# final_clock.net
KiCad netlist of a schematic drawn in Altium Designer
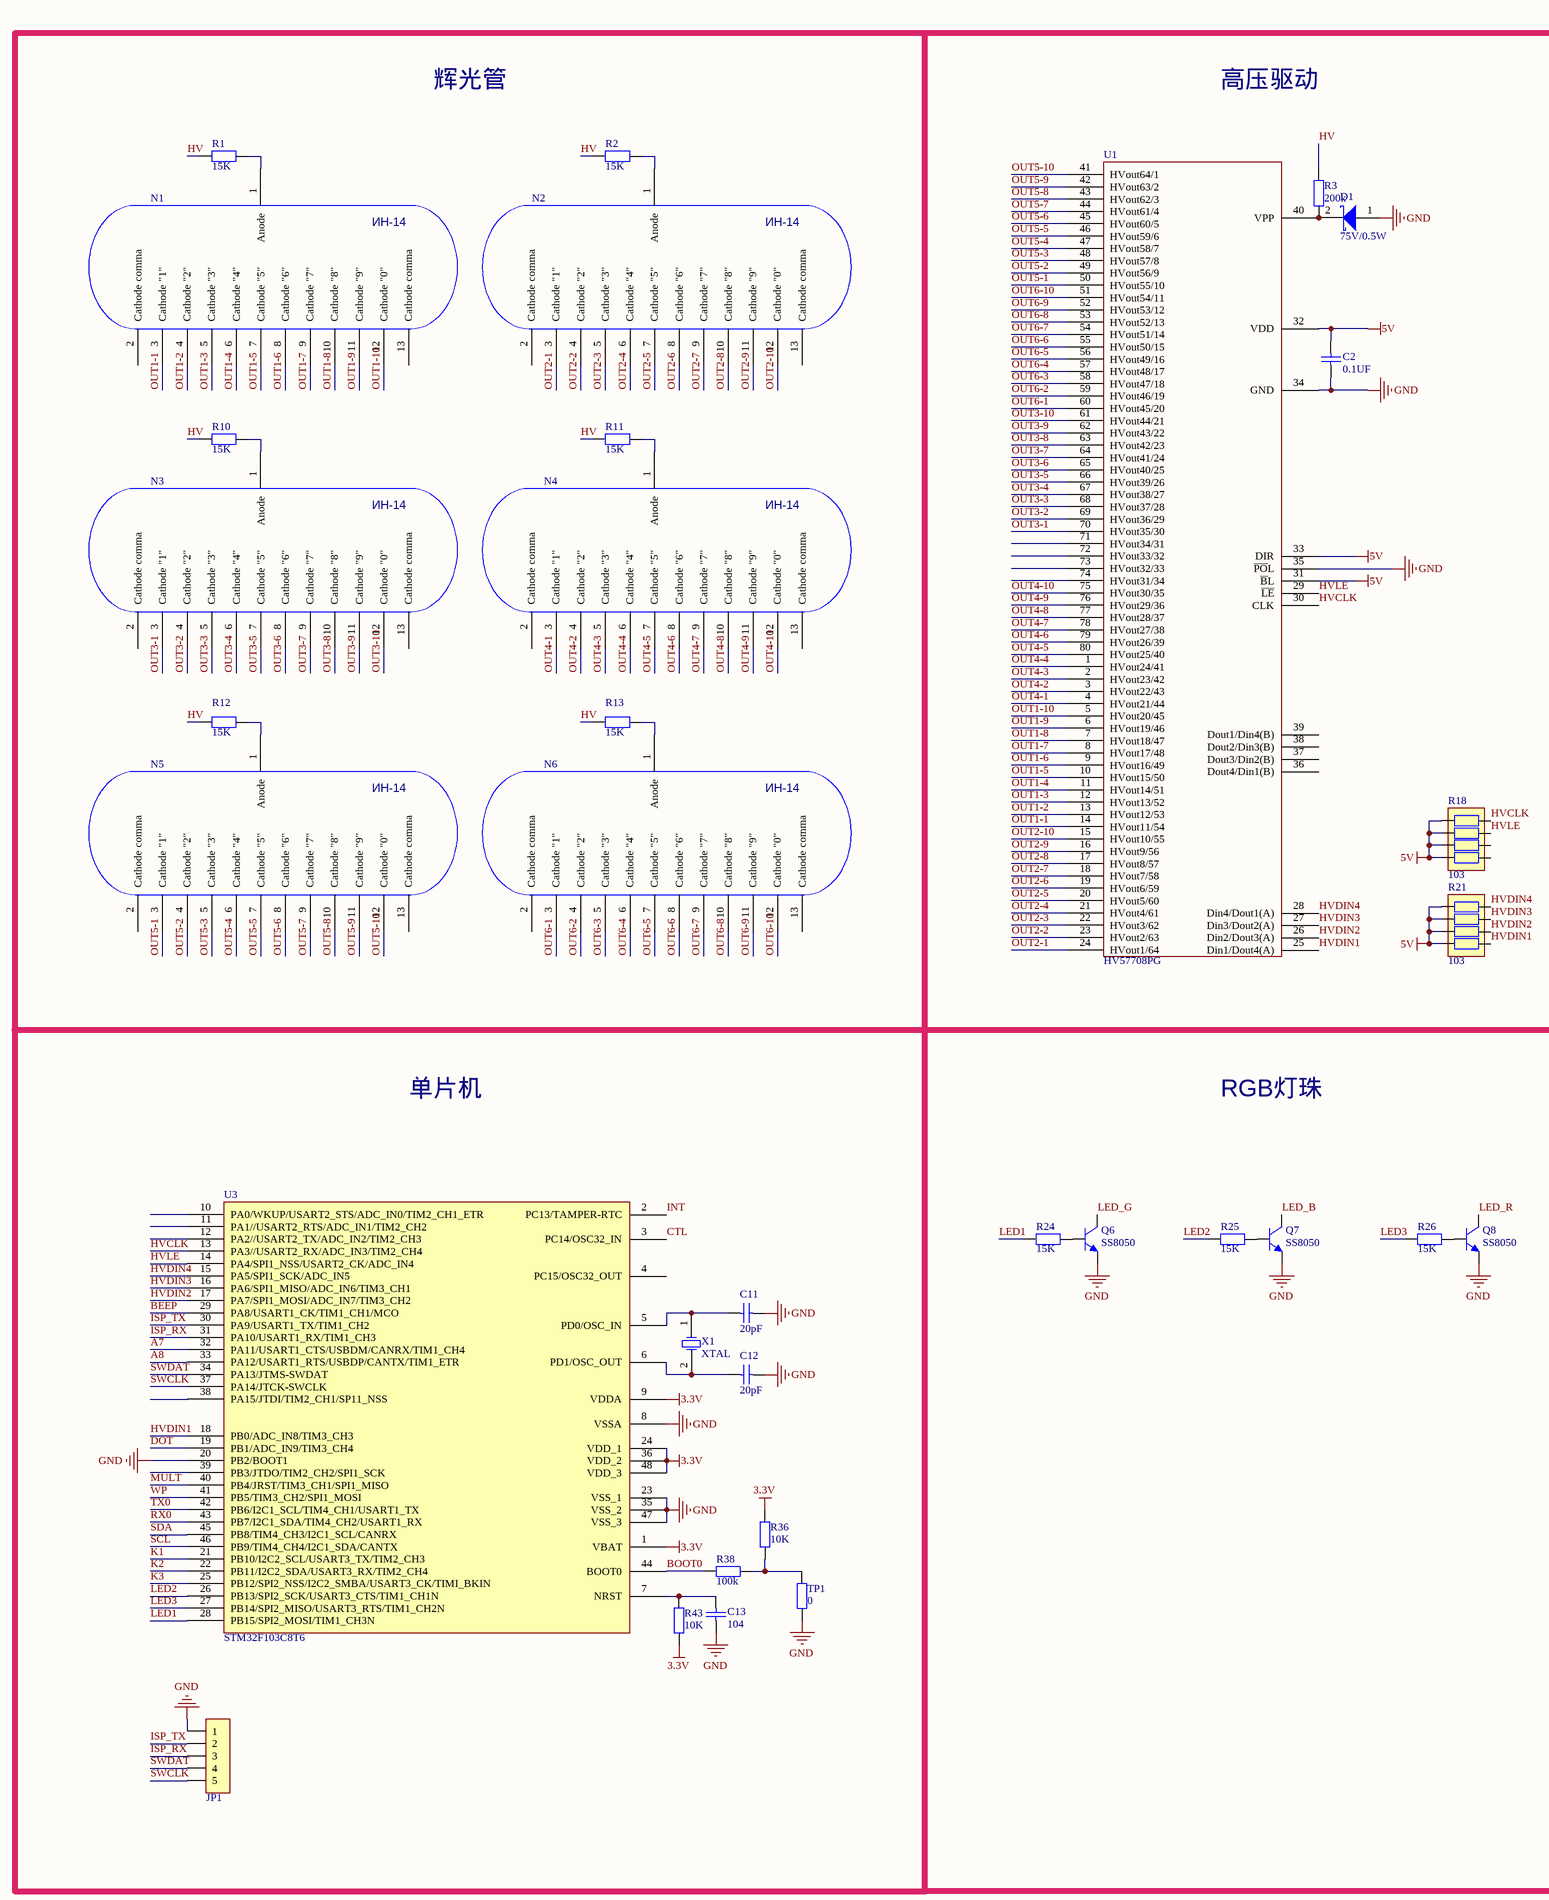
[diagram p0: final_clock.SchDoc, left]
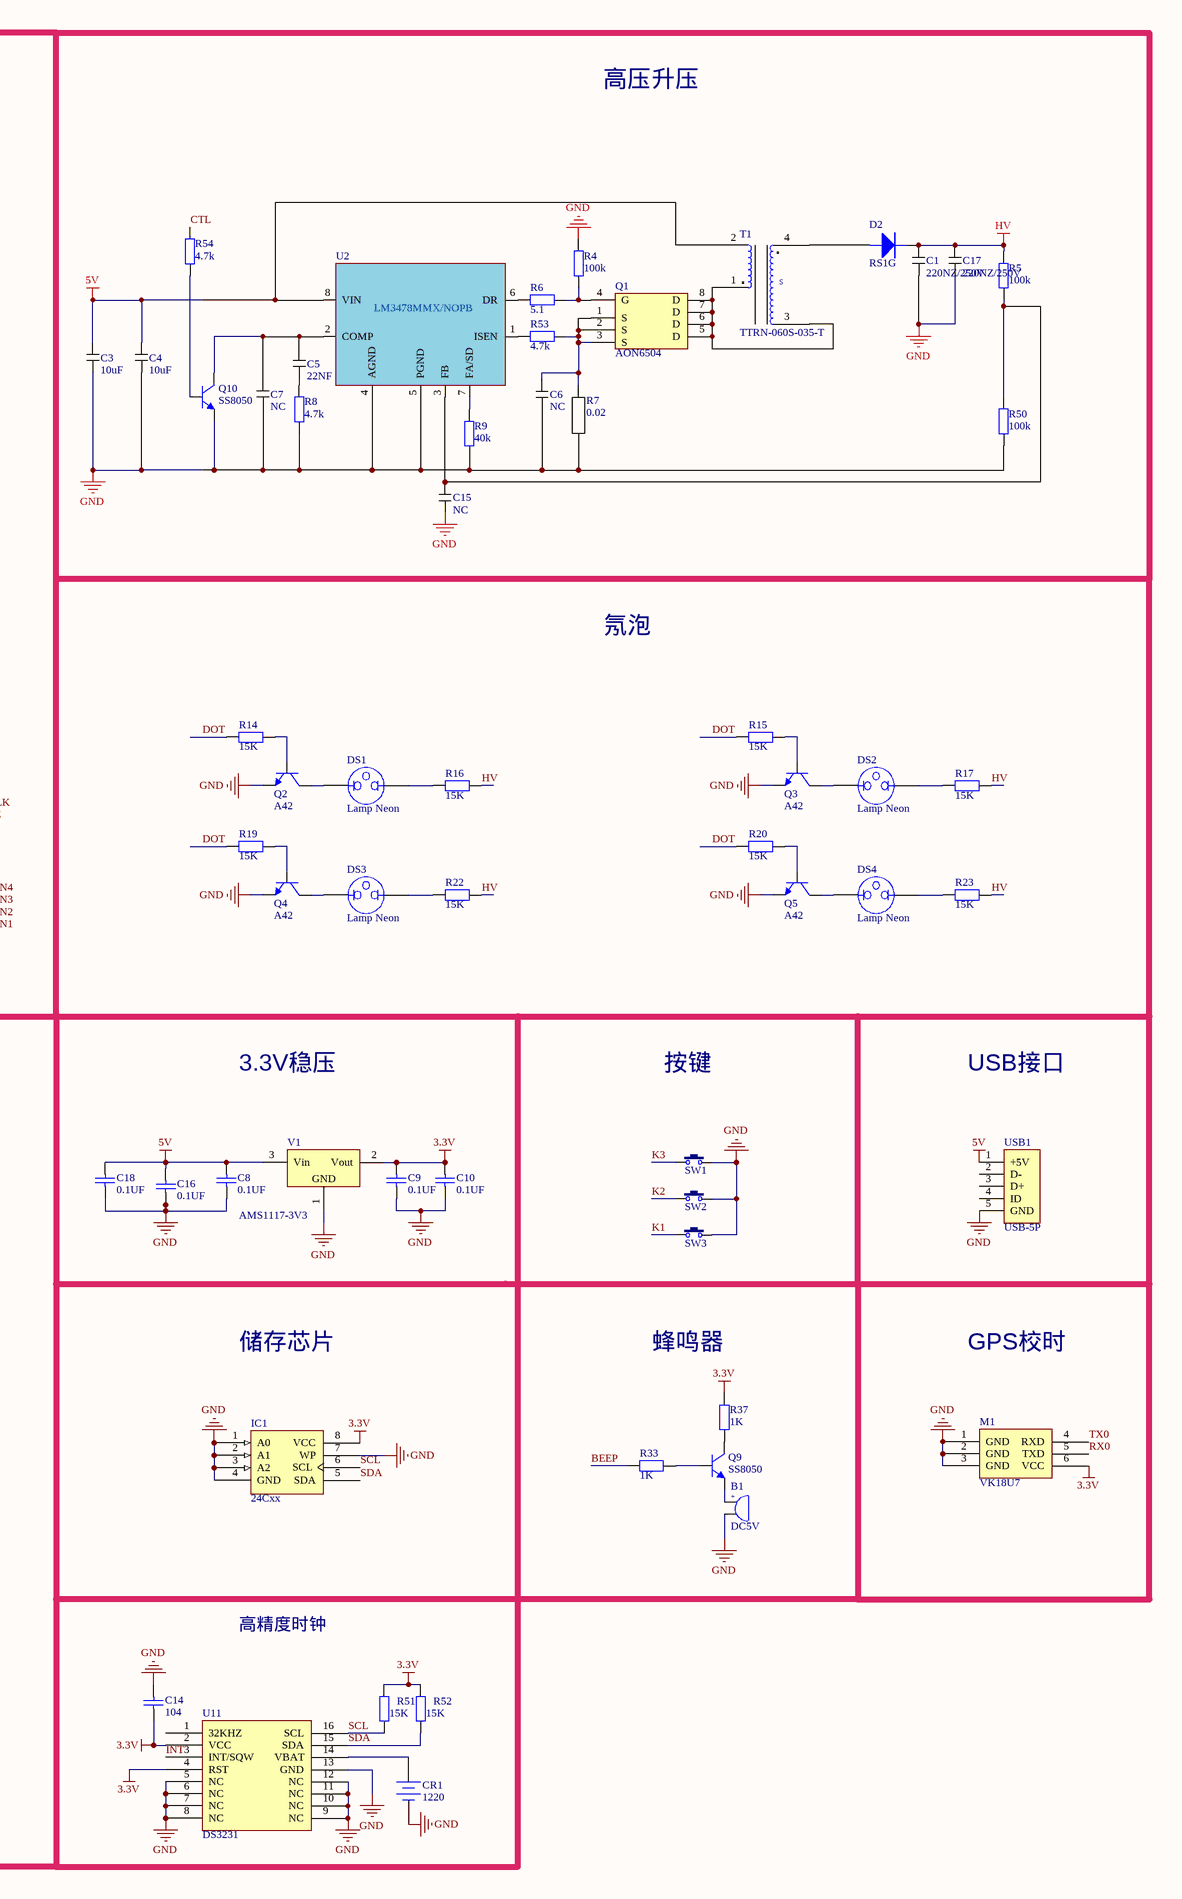
[diagram p1: final_clock.SchDoc, right]

(export (version "E")
  (design (tool "Eeschema 10.0.6"))
  (components
    (comp (ref "B1")
      (value "DC5V")
      (footprint "贴片蜂鸣器")
      (description "蜂鸣器")
      (fields (field (name "版权归属") "源创客"))
      (libsource (lib "未分类器件") (part "BEEP"))
    )
    (comp (ref "C1")
      (value "220NZ/250V")
      (footprint "C 1812")
      (description "无极性电容")
      (libsource (lib "贴片电容") (part "CAP"))
    )
    (comp (ref "C2")
      (value "0.1UF")
      (footprint "C 0805")
      (description "Capacitor")
      (fields (field (name "Comment") "Cap") (field (name "PUBLISHER") "Altium Limited"))
      (libsource (lib "Miscellaneous Devices") (part "Cap"))
    )
    (comp (ref "C3")
      (value "10uF")
      (footprint "C 1812")
      (description "无极性电容")
      (libsource (lib "贴片电容") (part "CAP"))
    )
    (comp (ref "C4")
      (value "10uF")
      (footprint "C 1812")
      (description "无极性电容")
      (libsource (lib "贴片电容") (part "CAP"))
    )
    (comp (ref "C5")
      (value "22NF")
      (footprint "C 0805")
      (description "无极性电容")
      (libsource (lib "贴片电容") (part "CAP"))
    )
    (comp (ref "C6")
      (value "NC")
      (footprint "C 0805")
      (description "无极性电容")
      (libsource (lib "贴片电容") (part "CAP"))
    )
    (comp (ref "C7")
      (value "NC")
      (footprint "C 0805")
      (description "无极性电容")
      (libsource (lib "贴片电容") (part "CAP"))
    )
    (comp (ref "C8")
      (value "0.1UF")
      (footprint "C 0805")
      (description "Capacitor")
      (fields (field (name "Comment") "Cap") (field (name "PUBLISHER") "Altium Limited"))
      (libsource (lib "Miscellaneous Devices") (part "Cap"))
    )
    (comp (ref "C9")
      (value "0.1UF")
      (footprint "C 0805")
      (description "Capacitor")
      (fields (field (name "Comment") "Cap") (field (name "PUBLISHER") "Altium Limited"))
      (libsource (lib "Miscellaneous Devices") (part "Cap"))
    )
    (comp (ref "C10")
      (value "0.1UF")
      (footprint "C 0805")
      (description "Capacitor")
      (fields (field (name "Comment") "Cap") (field (name "PUBLISHER") "Altium Limited"))
      (libsource (lib "Miscellaneous Devices") (part "Cap"))
    )
    (comp (ref "C11")
      (value "20pF")
      (footprint "C 0805")
      (description "Capacitor")
      (fields (field (name "Comment") "Cap") (field (name "PUBLISHER") "Altium Limited"))
      (libsource (lib "Miscellaneous Devices") (part "Cap"))
    )
    (comp (ref "C12")
      (value "20pF")
      (footprint "C 0805")
      (description "Capacitor")
      (fields (field (name "Comment") "Cap") (field (name "PUBLISHER") "Altium Limited"))
      (libsource (lib "Miscellaneous Devices") (part "Cap"))
    )
    (comp (ref "C13")
      (value "104")
      (footprint "C 0805")
      (description "Capacitor")
      (fields (field (name "Comment") "Cap") (field (name "PUBLISHER") "Altium Limited"))
      (libsource (lib "Miscellaneous Devices") (part "Cap"))
    )
    (comp (ref "C14")
      (value "104")
      (footprint "C 0805")
      (description "Capacitor")
      (fields (field (name "Comment") "Cap") (field (name "PUBLISHER") "Altium Limited"))
      (libsource (lib "Miscellaneous Devices") (part "Cap"))
    )
    (comp (ref "C15")
      (value "NC")
      (footprint "C 0805")
      (description "无极性电容")
      (libsource (lib "贴片电容") (part "CAP"))
    )
    (comp (ref "C16")
      (value "0.1UF")
      (footprint "C 0805")
      (description "Capacitor")
      (fields (field (name "Comment") "Cap") (field (name "PUBLISHER") "Altium Limited"))
      (libsource (lib "Miscellaneous Devices") (part "Cap"))
    )
    (comp (ref "C17")
      (value "220NZ/250V")
      (footprint "C 1812")
      (description "无极性电容")
      (libsource (lib "贴片电容") (part "CAP"))
    )
    (comp (ref "C18")
      (value "0.1UF")
      (footprint "C 0805")
      (description "Capacitor")
      (fields (field (name "Comment") "Cap") (field (name "PUBLISHER") "Altium Limited"))
      (libsource (lib "Miscellaneous Devices") (part "Cap"))
    )
    (comp (ref "CR1")
      (value "1220")
      (footprint "CR1220_A")
      (description "微型电池")
      (fields (field (name "版权归属") "源创客"))
      (libsource (lib "未分类器件") (part "CR-3V"))
    )
    (comp (ref "D1")
      (value "75V/0.5W")
      (footprint "R 1206")
      (description "Schottky Rectifier")
      (fields (field (name "PUBLISHER") "Altium Limited"))
      (libsource (lib "Miscellaneous Devices") (part "Diode 10TQ040"))
    )
    (comp (ref "D2")
      (value "RS1G")
      (footprint "SMA")
      (description "贴片快恢复二极管")
      (libsource (lib "二极管") (part "RS1G"))
    )
    (comp (ref "DS1")
      (value "Lamp Neon")
      (footprint "LED_PIN2")
      (description "Neon Lamp")
      (fields (field (name "PUBLISHER") "Altium Limited"))
      (libsource (lib "Miscellaneous Devices") (part "Lamp Neon"))
    )
    (comp (ref "DS2")
      (value "Lamp Neon")
      (footprint "LED_PIN2")
      (description "Neon Lamp")
      (fields (field (name "PUBLISHER") "Altium Limited"))
      (libsource (lib "Miscellaneous Devices") (part "Lamp Neon"))
    )
    (comp (ref "DS3")
      (value "Lamp Neon")
      (footprint "LED_PIN2")
      (description "Neon Lamp")
      (fields (field (name "PUBLISHER") "Altium Limited"))
      (libsource (lib "Miscellaneous Devices") (part "Lamp Neon"))
    )
    (comp (ref "DS4")
      (value "Lamp Neon")
      (footprint "LED_PIN2")
      (description "Neon Lamp")
      (fields (field (name "PUBLISHER") "Altium Limited"))
      (libsource (lib "Miscellaneous Devices") (part "Lamp Neon"))
    )
    (comp (ref "IC1")
      (value "24Cxx")
      (footprint "SOP8_L")
      (description "外置EEPROM")
      (fields (field (name "版权归属") "源创客"))
      (libsource (lib "IC芯片") (part "24Cxx"))
    )
    (comp (ref "JP1")
      (value "HDR-1X5")
      (footprint "HDR-1X5")
      (description "5P接插件")
      (fields (field (name "版权归属") "源创客"))
      (libsource (lib "接插件") (part "Header 5"))
    )
    (comp (ref "M1") (value "VK18U7") (footprint "VK18U7") (libsource (lib "module_lib") (part "VK18U7")))
    (comp (ref "N1") (value "ИН-14") (footprint "IN14") (libsource (lib "NIXIEClock_SCHLib") (part "ИН-14")))
    (comp (ref "N2") (value "ИН-14") (footprint "IN14") (libsource (lib "NIXIEClock_SCHLib") (part "ИН-14")))
    (comp (ref "N3") (value "ИН-14") (footprint "IN14") (libsource (lib "NIXIEClock_SCHLib") (part "ИН-14")))
    (comp (ref "N4") (value "ИН-14") (footprint "IN14") (libsource (lib "NIXIEClock_SCHLib") (part "ИН-14")))
    (comp (ref "N5") (value "ИН-14") (footprint "IN14") (libsource (lib "NIXIEClock_SCHLib") (part "ИН-14")))
    (comp (ref "N6") (value "ИН-14") (footprint "IN14") (libsource (lib "NIXIEClock_SCHLib") (part "ИН-14")))
    (comp (ref "Q1")
      (value "AON6504")
      (footprint "DFN-MOS")
      (description "N沟道MOS管")
      (libsource (lib "MOS管") (part "AON6504"))
    )
    (comp (ref "Q2")
      (value "A42")
      (footprint "SOT23-3L")
      (description "高频放大-NPN型")
      (fields (field (name "版权归属") "源创客"))
      (libsource (lib "三极管") (part "8050-SMD"))
    )
    (comp (ref "Q3")
      (value "A42")
      (footprint "SOT23-3L")
      (description "高频放大-NPN型")
      (fields (field (name "版权归属") "源创客"))
      (libsource (lib "三极管") (part "8050-SMD"))
    )
    (comp (ref "Q4")
      (value "A42")
      (footprint "SOT23-3L")
      (description "高频放大-NPN型")
      (fields (field (name "版权归属") "源创客"))
      (libsource (lib "三极管") (part "8050-SMD"))
    )
    (comp (ref "Q5")
      (value "A42")
      (footprint "SOT23-3L")
      (description "高频放大-NPN型")
      (fields (field (name "版权归属") "源创客"))
      (libsource (lib "三极管") (part "8050-SMD"))
    )
    (comp (ref "Q6")
      (value "SS8050")
      (footprint "SOT23-3L")
      (description "高频放大-NPN型")
      (fields (field (name "版权归属") "源创客"))
      (libsource (lib "三极管") (part "8050-SMD"))
    )
    (comp (ref "Q7")
      (value "SS8050")
      (footprint "SOT23-3L")
      (description "高频放大-NPN型")
      (fields (field (name "版权归属") "源创客"))
      (libsource (lib "三极管") (part "8050-SMD"))
    )
    (comp (ref "Q8")
      (value "SS8050")
      (footprint "SOT23-3L")
      (description "高频放大-NPN型")
      (fields (field (name "版权归属") "源创客"))
      (libsource (lib "三极管") (part "8050-SMD"))
    )
    (comp (ref "Q9")
      (value "SS8050")
      (footprint "SOT23-3L")
      (description "高频放大-NPN型")
      (fields (field (name "版权归属") "源创客"))
      (libsource (lib "三极管") (part "8050-SMD"))
    )
    (comp (ref "Q10")
      (value "SS8050")
      (footprint "SOT23-3L")
      (description "高频放大-NPN型")
      (fields (field (name "版权归属") "源创客"))
      (libsource (lib "三极管") (part "8050-SMD"))
    )
    (comp (ref "R1")
      (value "15K")
      (footprint "R 0805")
      (description "Resistor")
      (fields (field (name "Comment") "Res2") (field (name "PUBLISHER") "Altium Limited"))
      (libsource (lib "") (part "Res2_2"))
    )
    (comp (ref "R2")
      (value "15K")
      (footprint "R 0805")
      (description "Resistor")
      (fields (field (name "Comment") "Res2") (field (name "PUBLISHER") "Altium Limited"))
      (libsource (lib "") (part "Res2_2"))
    )
    (comp (ref "R3")
      (value "200k")
      (footprint "R 0805")
      (description "Resistor")
      (fields (field (name "Comment") "Res2") (field (name "PUBLISHER") "Altium Limited"))
      (libsource (lib "") (part "Res2_1"))
    )
    (comp (ref "R4")
      (value "100k")
      (footprint "R 0805")
      (description "Resistor")
      (fields (field (name "Comment") "Res2") (field (name "PUBLISHER") "Altium Limited"))
      (libsource (lib "") (part "Res2_1"))
    )
    (comp (ref "R5")
      (value "100k")
      (footprint "R 0805")
      (description "Resistor")
      (fields (field (name "Comment") "Res2") (field (name "PUBLISHER") "Altium Limited"))
      (libsource (lib "") (part "Res2_1"))
    )
    (comp (ref "R6")
      (value "5.1")
      (footprint "R 0805")
      (description "Resistor")
      (fields (field (name "Comment") "Res2") (field (name "PUBLISHER") "Altium Limited"))
      (libsource (lib "Miscellaneous Devices") (part "Res2"))
    )
    (comp (ref "R7") (value "0.02") (footprint "R 1206") (libsource (lib "贴片电阻") (part "RES")))
    (comp (ref "R8")
      (value "4.7k")
      (footprint "R 0805")
      (description "Resistor")
      (fields (field (name "Comment") "Res2") (field (name "PUBLISHER") "Altium Limited"))
      (libsource (lib "") (part "Res2_1"))
    )
    (comp (ref "R9")
      (value "40k")
      (footprint "R 0805")
      (description "Resistor")
      (fields (field (name "Comment") "Res2") (field (name "PUBLISHER") "Altium Limited"))
      (libsource (lib "") (part "Res2_1"))
    )
    (comp (ref "R10")
      (value "15K")
      (footprint "R 0805")
      (description "Resistor")
      (fields (field (name "Comment") "Res2") (field (name "PUBLISHER") "Altium Limited"))
      (libsource (lib "") (part "Res2_2"))
    )
    (comp (ref "R11")
      (value "15K")
      (footprint "R 0805")
      (description "Resistor")
      (fields (field (name "Comment") "Res2") (field (name "PUBLISHER") "Altium Limited"))
      (libsource (lib "") (part "Res2_2"))
    )
    (comp (ref "R12")
      (value "15K")
      (footprint "R 0805")
      (description "Resistor")
      (fields (field (name "Comment") "Res2") (field (name "PUBLISHER") "Altium Limited"))
      (libsource (lib "") (part "Res2_2"))
    )
    (comp (ref "R13")
      (value "15K")
      (footprint "R 0805")
      (description "Resistor")
      (fields (field (name "Comment") "Res2") (field (name "PUBLISHER") "Altium Limited"))
      (libsource (lib "") (part "Res2_2"))
    )
    (comp (ref "R14")
      (value "15K")
      (footprint "R 0805")
      (description "Resistor")
      (fields (field (name "Comment") "Res2") (field (name "PUBLISHER") "Altium Limited"))
      (libsource (lib "") (part "Res2_2"))
    )
    (comp (ref "R15")
      (value "15K")
      (footprint "R 0805")
      (description "Resistor")
      (fields (field (name "Comment") "Res2") (field (name "PUBLISHER") "Altium Limited"))
      (libsource (lib "") (part "Res2_2"))
    )
    (comp (ref "R16")
      (value "15K")
      (footprint "R 0805")
      (description "Resistor")
      (fields (field (name "Comment") "Res2") (field (name "PUBLISHER") "Altium Limited"))
      (libsource (lib "") (part "Res2_2"))
    )
    (comp (ref "R17")
      (value "15K")
      (footprint "R 0805")
      (description "Resistor")
      (fields (field (name "Comment") "Res2") (field (name "PUBLISHER") "Altium Limited"))
      (libsource (lib "") (part "Res2_2"))
    )
    (comp (ref "R18")
      (value "103")
      (footprint "RCA-8P4R-0603")
      (description "贴片网络排阻")
      (fields (field (name "版权归属") "源创客"))
      (libsource (lib "电阻-电容-电感") (part "R-8P4R"))
    )
    (comp (ref "R19")
      (value "15K")
      (footprint "R 0805")
      (description "Resistor")
      (fields (field (name "Comment") "Res2") (field (name "PUBLISHER") "Altium Limited"))
      (libsource (lib "") (part "Res2_2"))
    )
    (comp (ref "R20")
      (value "15K")
      (footprint "R 0805")
      (description "Resistor")
      (fields (field (name "Comment") "Res2") (field (name "PUBLISHER") "Altium Limited"))
      (libsource (lib "") (part "Res2_2"))
    )
    (comp (ref "R21")
      (value "103")
      (footprint "RCA-8P4R-0603")
      (description "贴片网络排阻")
      (fields (field (name "版权归属") "源创客"))
      (libsource (lib "电阻-电容-电感") (part "R-8P4R"))
    )
    (comp (ref "R22")
      (value "15K")
      (footprint "R 0805")
      (description "Resistor")
      (fields (field (name "Comment") "Res2") (field (name "PUBLISHER") "Altium Limited"))
      (libsource (lib "") (part "Res2_2"))
    )
    (comp (ref "R23")
      (value "15K")
      (footprint "R 0805")
      (description "Resistor")
      (fields (field (name "Comment") "Res2") (field (name "PUBLISHER") "Altium Limited"))
      (libsource (lib "") (part "Res2_2"))
    )
    (comp (ref "R24")
      (value "15K")
      (footprint "R 0805")
      (description "Resistor")
      (fields (field (name "Comment") "Res2") (field (name "PUBLISHER") "Altium Limited"))
      (libsource (lib "") (part "Res2_2"))
    )
    (comp (ref "R25")
      (value "15K")
      (footprint "R 0805")
      (description "Resistor")
      (fields (field (name "Comment") "Res2") (field (name "PUBLISHER") "Altium Limited"))
      (libsource (lib "") (part "Res2_2"))
    )
    (comp (ref "R26")
      (value "15K")
      (footprint "R 0805")
      (description "Resistor")
      (fields (field (name "Comment") "Res2") (field (name "PUBLISHER") "Altium Limited"))
      (libsource (lib "") (part "Res2_2"))
    )
    (comp (ref "R33")
      (value "1K")
      (footprint "R 0805")
      (description "Resistor")
      (fields (field (name "Comment") "Res2") (field (name "PUBLISHER") "Altium Limited"))
      (libsource (lib "Miscellaneous Devices") (part "Res2"))
    )
    (comp (ref "R36")
      (value "10K")
      (footprint "R 0805")
      (description "Resistor")
      (fields (field (name "Comment") "Res2") (field (name "PUBLISHER") "Altium Limited"))
      (libsource (lib "") (part "Res2_3"))
    )
    (comp (ref "R37")
      (value "1K")
      (footprint "R 0805")
      (description "Resistor")
      (fields (field (name "Comment") "Res2") (field (name "PUBLISHER") "Altium Limited"))
      (libsource (lib "") (part "Res2_3"))
    )
    (comp (ref "R38")
      (value "100k")
      (footprint "R 0805")
      (description "Resistor")
      (fields (field (name "Comment") "Res2") (field (name "PUBLISHER") "Altium Limited"))
      (libsource (lib "Miscellaneous Devices") (part "Res2"))
    )
    (comp (ref "R43")
      (value "10K")
      (footprint "R 0805")
      (description "Resistor")
      (fields (field (name "Comment") "Res2") (field (name "PUBLISHER") "Altium Limited"))
      (libsource (lib "") (part "Res2_1"))
    )
    (comp (ref "R50")
      (value "100k")
      (footprint "R 0805")
      (description "Resistor")
      (fields (field (name "Comment") "Res2") (field (name "PUBLISHER") "Altium Limited"))
      (libsource (lib "") (part "Res2_1"))
    )
    (comp (ref "R51")
      (value "15K")
      (footprint "R 0805")
      (description "Resistor")
      (fields (field (name "Comment") "Res2") (field (name "PUBLISHER") "Altium Limited"))
      (libsource (lib "") (part "Res2_1"))
    )
    (comp (ref "R52")
      (value "15K")
      (footprint "R 0805")
      (description "Resistor")
      (fields (field (name "Comment") "Res2") (field (name "PUBLISHER") "Altium Limited"))
      (libsource (lib "") (part "Res2_1"))
    )
    (comp (ref "R53")
      (value "4.7k")
      (footprint "R 0805")
      (description "Resistor")
      (fields (field (name "Comment") "Res2") (field (name "PUBLISHER") "Altium Limited"))
      (libsource (lib "Miscellaneous Devices") (part "Res2"))
    )
    (comp (ref "R54")
      (value "4.7k")
      (footprint "R 0805")
      (description "Resistor")
      (fields (field (name "Comment") "Res2") (field (name "PUBLISHER") "Altium Limited"))
      (libsource (lib "") (part "Res2_3"))
    )
    (comp (ref "SW1")
      (value "3x6x5")
      (footprint "贴片侧式按键")
      (description "3x6轻触开关")
      (fields (field (name "版权归属") "源创客"))
      (libsource (lib "按键-开关") (part "TSW 3x6"))
    )
    (comp (ref "SW2")
      (value "3x6x5")
      (footprint "贴片侧式按键")
      (description "3x6轻触开关")
      (fields (field (name "版权归属") "源创客"))
      (libsource (lib "按键-开关") (part "TSW 3x6"))
    )
    (comp (ref "SW3")
      (value "3x6x5")
      (footprint "贴片侧式按键")
      (description "3x6轻触开关")
      (fields (field (name "版权归属") "源创客"))
      (libsource (lib "按键-开关") (part "TSW 3x6"))
    )
    (comp (ref "T1")
      (value "TTRN-060S-035-T")
      (footprint "EE5.0")
      (description "闪光灯变压器")
      (libsource (lib "变压器") (part "TTRN-060S-035-T"))
    )
    (comp (ref "TP1")
      (value "0")
      (footprint "R 0805")
      (description "Resistor")
      (fields (field (name "Comment") "Res2") (field (name "PUBLISHER") "Altium Limited"))
      (libsource (lib "") (part "Res2_3"))
    )
    (comp (ref "U1") (value "HV57708PG") (footprint "CQFP80") (libsource (lib "SCH") (part "HV57708PG")))
    (comp (ref "U2")
      (value "LM3478MM")
      (footprint "SSOP8_N")
      (description "开关电源芯片")
      (fields
        (field (name "MANUFACTURER PART NUMBER") "LM3478MM/NOPB")
        (field (name "PACKAGEREFERENCE") "LM3478MMX/NOPB")
      )
      (libsource (lib "电源模块") (part "LM3478MM"))
    )
    (comp (ref "U3")
      (value "STM32F103C8T6")
      (footprint "LQFP48 7X7_N")
      (libsource (lib "Personal_Accumulation_Sch") (part "STM32F103C8T6"))
    )
    (comp (ref "U11") (value "DS3231") (footprint "SOP16W_M") (libsource (lib "ic_lib") (part "DS3231")))
    (comp (ref "USB1")
      (value "USB-5P")
      (footprint "USB-MICRO_A")
      (description "微型USB母座")
      (fields (field (name "版权归属") "源创客"))
      (libsource (lib "接口类") (part "USB-5P"))
    )
    (comp (ref "V1")
      (value "AMS1117-3V3")
      (footprint "_SOT-223")
      (description "三端稳压芯片")
      (fields (field (name "版权归属") "源创客"))
      (libsource (lib "IC芯片") (part "AMS1117"))
    )
    (comp (ref "X1")
      (value "XTAL")
      (footprint "5032-xtal")
      (description "Crystal Oscillator")
      (fields (field (name "PUBLISHER") "Altium Limited"))
      (libsource (lib "Miscellaneous Devices") (part "XTAL"))
    )
  )
  (nets
    (net (code "1") (name "/A7") (class "Default")
      (node (ref "U3") (pin "32") (pinfunction "PA11/USART1_CTS/USBDM/CANRX/TIM1_CH4_32") (pintype "passive"))
    )
    (net (code "2") (name "/A8") (class "Default")
      (node (ref "U3") (pin "33") (pinfunction "PA12/USART1_RTS/USBDP/CANTX/TIM1_ETR_33") (pintype "passive"))
    )
    (net (code "3") (name "/BEEP") (class "Default")
      (node (ref "R33") (pin "1") (pinfunction "1_1") (pintype "passive"))
      (node (ref "U3") (pin "29") (pinfunction "PA8/USART1_CK/TIM1_CH1/MCO_29") (pintype "passive"))
    )
    (net (code "4") (name "/BOOT0") (class "Default")
      (node (ref "R38") (pin "1") (pinfunction "1_1") (pintype "passive"))
      (node (ref "U3") (pin "44") (pinfunction "BOOT0_44") (pintype "passive"))
    )
    (net (code "5") (name "/CTL") (class "Default")
      (node (ref "R54") (pin "2") (pinfunction "2_2") (pintype "passive"))
      (node (ref "U3") (pin "3") (pinfunction "PC14/OSC32_IN_3") (pintype "passive"))
    )
    (net (code "6") (name "/DOT") (class "Default")
      (node (ref "R14") (pin "2") (pinfunction "2_2") (pintype "passive"))
      (node (ref "R15") (pin "2") (pinfunction "2_2") (pintype "passive"))
      (node (ref "R19") (pin "2") (pinfunction "2_2") (pintype "passive"))
      (node (ref "R20") (pin "2") (pinfunction "2_2") (pintype "passive"))
      (node (ref "U3") (pin "19") (pinfunction "PB1/ADC_IN9/TIM3_CH4_19") (pintype "passive"))
    )
    (net (code "7") (name "/HVCLK") (class "Default")
      (node (ref "R18") (pin "8") (pinfunction "8_8") (pintype "passive"))
      (node (ref "U1") (pin "30") (pinfunction "CLK_30") (pintype "passive"))
      (node (ref "U3") (pin "13") (pinfunction "PA3//USART2_RX/ADC_IN3/TIM2_CH4_13") (pintype "passive"))
    )
    (net (code "8") (name "/HVDIN1") (class "Default")
      (node (ref "R21") (pin "5") (pinfunction "5_5") (pintype "passive"))
      (node (ref "U1") (pin "25") (pinfunction "Din1/Dout4(A)_25") (pintype "passive"))
      (node (ref "U3") (pin "18") (pinfunction "PB0/ADC_IN8/TIM3_CH3_18") (pintype "passive"))
    )
    (net (code "9") (name "/HVDIN2") (class "Default")
      (node (ref "R21") (pin "6") (pinfunction "6_6") (pintype "passive"))
      (node (ref "U1") (pin "26") (pinfunction "Din2/Dout3(A)_26") (pintype "passive"))
      (node (ref "U3") (pin "17") (pinfunction "PA7/SPI1_MOSI/ADC_IN7/TIM3_CH2_17") (pintype "passive"))
    )
    (net (code "10") (name "/HVDIN3") (class "Default")
      (node (ref "R21") (pin "7") (pinfunction "7_7") (pintype "passive"))
      (node (ref "U1") (pin "27") (pinfunction "Din3/Dout2(A)_27") (pintype "passive"))
      (node (ref "U3") (pin "16") (pinfunction "PA6/SPI1_MISO/ADC_IN6/TIM3_CH1_16") (pintype "passive"))
    )
    (net (code "11") (name "/HVDIN4") (class "Default")
      (node (ref "R21") (pin "8") (pinfunction "8_8") (pintype "passive"))
      (node (ref "U1") (pin "28") (pinfunction "Din4/Dout1(A)_28") (pintype "passive"))
      (node (ref "U3") (pin "15") (pinfunction "PA5/SPI1_SCK/ADC_IN5_15") (pintype "passive"))
    )
    (net (code "12") (name "/HVLE") (class "Default")
      (node (ref "R18") (pin "7") (pinfunction "7_7") (pintype "passive"))
      (node (ref "U1") (pin "29") (pinfunction "~{LE}_29") (pintype "passive"))
      (node (ref "U3") (pin "14") (pinfunction "PA4/SPI1_NSS/USART2_CK/ADC_IN4_14") (pintype "passive"))
    )
    (net (code "13") (name "/INT") (class "Default")
      (node (ref "U11") (pin "3") (pinfunction "INT/SQW_3") (pintype "passive"))
      (node (ref "U3") (pin "2") (pinfunction "PC13/TAMPER-RTC_2") (pintype "passive"))
    )
    (net (code "14") (name "/ISP_RX") (class "Default")
      (node (ref "JP1") (pin "3") (pinfunction "3_3") (pintype "passive"))
      (node (ref "U3") (pin "31") (pinfunction "PA10/USART1_RX/TIM1_CH3_31") (pintype "passive"))
    )
    (net (code "15") (name "/ISP_TX") (class "Default")
      (node (ref "JP1") (pin "2") (pinfunction "2_2") (pintype "passive"))
      (node (ref "U3") (pin "30") (pinfunction "PA9/USART1_TX/TIM1_CH2_30") (pintype "passive"))
    )
    (net (code "16") (name "/K1") (class "Default")
      (node (ref "SW3") (pin "1") (pinfunction "1_1") (pintype "passive"))
      (node (ref "U3") (pin "21") (pinfunction "PB10/I2C2_SCL/USART3_TX/TIM2_CH3_21") (pintype "passive"))
    )
    (net (code "17") (name "/K2") (class "Default")
      (node (ref "SW2") (pin "1") (pinfunction "1_1") (pintype "passive"))
      (node (ref "U3") (pin "22") (pinfunction "PB11/I2C2_SDA/USART3_RX/TIM2_CH4_22") (pintype "passive"))
    )
    (net (code "18") (name "/K3") (class "Default")
      (node (ref "SW1") (pin "1") (pinfunction "1_1") (pintype "passive"))
      (node (ref "U3") (pin "25") (pinfunction "PB12/SPI2_NSS/I2C2_SMBA/USART3_CK/TIMI_BKIN_25") (pintype "passive"))
    )
    (net (code "19") (name "/LED1") (class "Default")
      (node (ref "R24") (pin "2") (pinfunction "2_2") (pintype "passive"))
      (node (ref "U3") (pin "28") (pinfunction "PB15/SPI2_MOSI/TIM1_CH3N_28") (pintype "passive"))
    )
    (net (code "20") (name "/LED2") (class "Default")
      (node (ref "R25") (pin "2") (pinfunction "2_2") (pintype "passive"))
      (node (ref "U3") (pin "26") (pinfunction "PB13/SPI2_SCK/USART3_CTS/TIM1_CH1N_26") (pintype "passive"))
    )
    (net (code "21") (name "/LED3") (class "Default")
      (node (ref "R26") (pin "2") (pinfunction "2_2") (pintype "passive"))
      (node (ref "U3") (pin "27") (pinfunction "PB14/SPI2_MISO/USART3_RTS/TIM1_CH2N_27") (pintype "passive"))
    )
    (net (code "22") (name "/LED_B") (class "Default")
      (node (ref "Q7") (pin "3") (pinfunction "C_3") (pintype "passive"))
    )
    (net (code "23") (name "/LED_G") (class "Default")
      (node (ref "Q6") (pin "3") (pinfunction "C_3") (pintype "passive"))
    )
    (net (code "24") (name "/LED_R") (class "Default")
      (node (ref "Q8") (pin "3") (pinfunction "C_3") (pintype "passive"))
    )
    (net (code "25") (name "/MULT") (class "Default")
      (node (ref "U3") (pin "40") (pinfunction "PB4/JRST/TIM3_CH1/SPI1_MISO_40") (pintype "passive"))
    )
    (net (code "26") (name "/OUT1-1") (class "Default")
      (node (ref "N1") (pin "3") (pinfunction "Cathode_\"1\"_3") (pintype "passive"))
      (node (ref "U1") (pin "14") (pinfunction "HVout11/54_14") (pintype "passive"))
    )
    (net (code "27") (name "/OUT1-2") (class "Default")
      (node (ref "N1") (pin "4") (pinfunction "Cathode_\"2\"_4") (pintype "passive"))
      (node (ref "U1") (pin "13") (pinfunction "HVout12/53_13") (pintype "passive"))
    )
    (net (code "28") (name "/OUT1-3") (class "Default")
      (node (ref "N1") (pin "5") (pinfunction "Cathode_\"3\"_5") (pintype "passive"))
      (node (ref "U1") (pin "12") (pinfunction "HVout13/52_12") (pintype "passive"))
    )
    (net (code "29") (name "/OUT1-4") (class "Default")
      (node (ref "N1") (pin "6") (pinfunction "Cathode_\"4\"_6") (pintype "passive"))
      (node (ref "U1") (pin "11") (pinfunction "HVout14/51_11") (pintype "passive"))
    )
    (net (code "30") (name "/OUT1-5") (class "Default")
      (node (ref "N1") (pin "7") (pinfunction "Cathode_\"5\"_7") (pintype "passive"))
      (node (ref "U1") (pin "10") (pinfunction "HVout15/50_10") (pintype "passive"))
    )
    (net (code "31") (name "/OUT1-6") (class "Default")
      (node (ref "N1") (pin "8") (pinfunction "Cathode_\"6\"_8") (pintype "passive"))
      (node (ref "U1") (pin "9") (pinfunction "HVout16/49_9") (pintype "passive"))
    )
    (net (code "32") (name "/OUT1-7") (class "Default")
      (node (ref "N1") (pin "9") (pinfunction "Cathode_\"7\"_9") (pintype "passive"))
      (node (ref "U1") (pin "8") (pinfunction "HVout17/48_8") (pintype "passive"))
    )
    (net (code "33") (name "/OUT1-8") (class "Default")
      (node (ref "N1") (pin "10") (pinfunction "Cathode_\"8\"_10") (pintype "passive"))
      (node (ref "U1") (pin "7") (pinfunction "HVout18/47_7") (pintype "passive"))
    )
    (net (code "34") (name "/OUT1-9") (class "Default")
      (node (ref "N1") (pin "11") (pinfunction "Cathode_\"9\"_11") (pintype "passive"))
      (node (ref "U1") (pin "6") (pinfunction "HVout19/46_6") (pintype "passive"))
    )
    (net (code "35") (name "/OUT1-10") (class "Default")
      (node (ref "N1") (pin "12") (pinfunction "Cathode_\"0\"_12") (pintype "passive"))
      (node (ref "U1") (pin "5") (pinfunction "HVout20/45_5") (pintype "passive"))
    )
    (net (code "36") (name "/OUT2-1") (class "Default")
      (node (ref "N2") (pin "3") (pinfunction "Cathode_\"1\"_3") (pintype "passive"))
      (node (ref "U1") (pin "24") (pinfunction "HVout1/64_24") (pintype "passive"))
    )
    (net (code "37") (name "/OUT2-2") (class "Default")
      (node (ref "N2") (pin "4") (pinfunction "Cathode_\"2\"_4") (pintype "passive"))
      (node (ref "U1") (pin "23") (pinfunction "HVout2/63_23") (pintype "passive"))
    )
    (net (code "38") (name "/OUT2-3") (class "Default")
      (node (ref "N2") (pin "5") (pinfunction "Cathode_\"3\"_5") (pintype "passive"))
      (node (ref "U1") (pin "22") (pinfunction "HVout3/62_22") (pintype "passive"))
    )
    (net (code "39") (name "/OUT2-4") (class "Default")
      (node (ref "N2") (pin "6") (pinfunction "Cathode_\"4\"_6") (pintype "passive"))
      (node (ref "U1") (pin "21") (pinfunction "HVout4/61_21") (pintype "passive"))
    )
    (net (code "40") (name "/OUT2-5") (class "Default")
      (node (ref "N2") (pin "7") (pinfunction "Cathode_\"5\"_7") (pintype "passive"))
      (node (ref "U1") (pin "20") (pinfunction "HVout5/60_20") (pintype "passive"))
    )
    (net (code "41") (name "/OUT2-6") (class "Default")
      (node (ref "N2") (pin "8") (pinfunction "Cathode_\"6\"_8") (pintype "passive"))
      (node (ref "U1") (pin "19") (pinfunction "HVout6/59_19") (pintype "passive"))
    )
    (net (code "42") (name "/OUT2-7") (class "Default")
      (node (ref "N2") (pin "9") (pinfunction "Cathode_\"7\"_9") (pintype "passive"))
      (node (ref "U1") (pin "18") (pinfunction "HVout7/58_18") (pintype "passive"))
    )
    (net (code "43") (name "/OUT2-8") (class "Default")
      (node (ref "N2") (pin "10") (pinfunction "Cathode_\"8\"_10") (pintype "passive"))
      (node (ref "U1") (pin "17") (pinfunction "HVout8/57_17") (pintype "passive"))
    )
    (net (code "44") (name "/OUT2-9") (class "Default")
      (node (ref "N2") (pin "11") (pinfunction "Cathode_\"9\"_11") (pintype "passive"))
      (node (ref "U1") (pin "16") (pinfunction "HVout9/56_16") (pintype "passive"))
    )
    (net (code "45") (name "/OUT2-10") (class "Default")
      (node (ref "N2") (pin "12") (pinfunction "Cathode_\"0\"_12") (pintype "passive"))
      (node (ref "U1") (pin "15") (pinfunction "HVout10/55_15") (pintype "passive"))
    )
    (net (code "46") (name "/OUT3-1") (class "Default")
      (node (ref "N3") (pin "3") (pinfunction "Cathode_\"1\"_3") (pintype "passive"))
      (node (ref "U1") (pin "70") (pinfunction "HVout35/30_70") (pintype "passive"))
    )
    (net (code "47") (name "/OUT3-2") (class "Default")
      (node (ref "N3") (pin "4") (pinfunction "Cathode_\"2\"_4") (pintype "passive"))
      (node (ref "U1") (pin "69") (pinfunction "HVout36/29_69") (pintype "passive"))
    )
    (net (code "48") (name "/OUT3-3") (class "Default")
      (node (ref "N3") (pin "5") (pinfunction "Cathode_\"3\"_5") (pintype "passive"))
      (node (ref "U1") (pin "68") (pinfunction "HVout37/28_68") (pintype "passive"))
    )
    (net (code "49") (name "/OUT3-4") (class "Default")
      (node (ref "N3") (pin "6") (pinfunction "Cathode_\"4\"_6") (pintype "passive"))
      (node (ref "U1") (pin "67") (pinfunction "HVout38/27_67") (pintype "passive"))
    )
    (net (code "50") (name "/OUT3-5") (class "Default")
      (node (ref "N3") (pin "7") (pinfunction "Cathode_\"5\"_7") (pintype "passive"))
      (node (ref "U1") (pin "66") (pinfunction "HVout39/26_66") (pintype "passive"))
    )
    (net (code "51") (name "/OUT3-6") (class "Default")
      (node (ref "N3") (pin "8") (pinfunction "Cathode_\"6\"_8") (pintype "passive"))
      (node (ref "U1") (pin "65") (pinfunction "HVout40/25_65") (pintype "passive"))
    )
    (net (code "52") (name "/OUT3-7") (class "Default")
      (node (ref "N3") (pin "9") (pinfunction "Cathode_\"7\"_9") (pintype "passive"))
      (node (ref "U1") (pin "64") (pinfunction "HVout41/24_64") (pintype "passive"))
    )
    (net (code "53") (name "/OUT3-8") (class "Default")
      (node (ref "N3") (pin "10") (pinfunction "Cathode_\"8\"_10") (pintype "passive"))
      (node (ref "U1") (pin "63") (pinfunction "HVout42/23_63") (pintype "passive"))
    )
    (net (code "54") (name "/OUT3-9") (class "Default")
      (node (ref "N3") (pin "11") (pinfunction "Cathode_\"9\"_11") (pintype "passive"))
      (node (ref "U1") (pin "62") (pinfunction "HVout43/22_62") (pintype "passive"))
    )
    (net (code "55") (name "/OUT3-10") (class "Default")
      (node (ref "N3") (pin "12") (pinfunction "Cathode_\"0\"_12") (pintype "passive"))
      (node (ref "U1") (pin "61") (pinfunction "HVout44/21_61") (pintype "passive"))
    )
    (net (code "56") (name "/OUT4-1") (class "Default")
      (node (ref "N4") (pin "3") (pinfunction "Cathode_\"1\"_3") (pintype "passive"))
      (node (ref "U1") (pin "4") (pinfunction "HVout21/44_4") (pintype "passive"))
    )
    (net (code "57") (name "/OUT4-2") (class "Default")
      (node (ref "N4") (pin "4") (pinfunction "Cathode_\"2\"_4") (pintype "passive"))
      (node (ref "U1") (pin "3") (pinfunction "HVout22/43_3") (pintype "passive"))
    )
    (net (code "58") (name "/OUT4-3") (class "Default")
      (node (ref "N4") (pin "5") (pinfunction "Cathode_\"3\"_5") (pintype "passive"))
      (node (ref "U1") (pin "2") (pinfunction "HVout23/42_2") (pintype "passive"))
    )
    (net (code "59") (name "/OUT4-4") (class "Default")
      (node (ref "N4") (pin "6") (pinfunction "Cathode_\"4\"_6") (pintype "passive"))
      (node (ref "U1") (pin "1") (pinfunction "HVout24/41_1") (pintype "passive"))
    )
    (net (code "60") (name "/OUT4-5") (class "Default")
      (node (ref "N4") (pin "7") (pinfunction "Cathode_\"5\"_7") (pintype "passive"))
      (node (ref "U1") (pin "80") (pinfunction "HVout25/40_80") (pintype "passive"))
    )
    (net (code "61") (name "/OUT4-6") (class "Default")
      (node (ref "N4") (pin "8") (pinfunction "Cathode_\"6\"_8") (pintype "passive"))
      (node (ref "U1") (pin "79") (pinfunction "HVout26/39_79") (pintype "passive"))
    )
    (net (code "62") (name "/OUT4-7") (class "Default")
      (node (ref "N4") (pin "9") (pinfunction "Cathode_\"7\"_9") (pintype "passive"))
      (node (ref "U1") (pin "78") (pinfunction "HVout27/38_78") (pintype "passive"))
    )
    (net (code "63") (name "/OUT4-8") (class "Default")
      (node (ref "N4") (pin "10") (pinfunction "Cathode_\"8\"_10") (pintype "passive"))
      (node (ref "U1") (pin "77") (pinfunction "HVout28/37_77") (pintype "passive"))
    )
    (net (code "64") (name "/OUT4-9") (class "Default")
      (node (ref "N4") (pin "11") (pinfunction "Cathode_\"9\"_11") (pintype "passive"))
      (node (ref "U1") (pin "76") (pinfunction "HVout29/36_76") (pintype "passive"))
    )
    (net (code "65") (name "/OUT4-10") (class "Default")
      (node (ref "N4") (pin "12") (pinfunction "Cathode_\"0\"_12") (pintype "passive"))
      (node (ref "U1") (pin "75") (pinfunction "HVout30/35_75") (pintype "passive"))
    )
    (net (code "66") (name "/OUT5-1") (class "Default")
      (node (ref "N5") (pin "3") (pinfunction "Cathode_\"1\"_3") (pintype "passive"))
      (node (ref "U1") (pin "50") (pinfunction "HVout55/10_50") (pintype "passive"))
    )
    (net (code "67") (name "/OUT5-2") (class "Default")
      (node (ref "N5") (pin "4") (pinfunction "Cathode_\"2\"_4") (pintype "passive"))
      (node (ref "U1") (pin "49") (pinfunction "HVout56/9_49") (pintype "passive"))
    )
    (net (code "68") (name "/OUT5-3") (class "Default")
      (node (ref "N5") (pin "5") (pinfunction "Cathode_\"3\"_5") (pintype "passive"))
      (node (ref "U1") (pin "48") (pinfunction "HVout57/8_48") (pintype "passive"))
    )
    (net (code "69") (name "/OUT5-4") (class "Default")
      (node (ref "N5") (pin "6") (pinfunction "Cathode_\"4\"_6") (pintype "passive"))
      (node (ref "U1") (pin "47") (pinfunction "HVout58/7_47") (pintype "passive"))
    )
    (net (code "70") (name "/OUT5-5") (class "Default")
      (node (ref "N5") (pin "7") (pinfunction "Cathode_\"5\"_7") (pintype "passive"))
      (node (ref "U1") (pin "46") (pinfunction "HVout59/6_46") (pintype "passive"))
    )
    (net (code "71") (name "/OUT5-6") (class "Default")
      (node (ref "N5") (pin "8") (pinfunction "Cathode_\"6\"_8") (pintype "passive"))
      (node (ref "U1") (pin "45") (pinfunction "HVout60/5_45") (pintype "passive"))
    )
    (net (code "72") (name "/OUT5-7") (class "Default")
      (node (ref "N5") (pin "9") (pinfunction "Cathode_\"7\"_9") (pintype "passive"))
      (node (ref "U1") (pin "44") (pinfunction "HVout61/4_44") (pintype "passive"))
    )
    (net (code "73") (name "/OUT5-8") (class "Default")
      (node (ref "N5") (pin "10") (pinfunction "Cathode_\"8\"_10") (pintype "passive"))
      (node (ref "U1") (pin "43") (pinfunction "HVout62/3_43") (pintype "passive"))
    )
    (net (code "74") (name "/OUT5-9") (class "Default")
      (node (ref "N5") (pin "11") (pinfunction "Cathode_\"9\"_11") (pintype "passive"))
      (node (ref "U1") (pin "42") (pinfunction "HVout63/2_42") (pintype "passive"))
    )
    (net (code "75") (name "/OUT5-10") (class "Default")
      (node (ref "N5") (pin "12") (pinfunction "Cathode_\"0\"_12") (pintype "passive"))
      (node (ref "U1") (pin "41") (pinfunction "HVout64/1_41") (pintype "passive"))
    )
    (net (code "76") (name "/OUT6-1") (class "Default")
      (node (ref "N6") (pin "3") (pinfunction "Cathode_\"1\"_3") (pintype "passive"))
      (node (ref "U1") (pin "60") (pinfunction "HVout45/20_60") (pintype "passive"))
    )
    (net (code "77") (name "/OUT6-2") (class "Default")
      (node (ref "N6") (pin "4") (pinfunction "Cathode_\"2\"_4") (pintype "passive"))
      (node (ref "U1") (pin "59") (pinfunction "HVout46/19_59") (pintype "passive"))
    )
    (net (code "78") (name "/OUT6-3") (class "Default")
      (node (ref "N6") (pin "5") (pinfunction "Cathode_\"3\"_5") (pintype "passive"))
      (node (ref "U1") (pin "58") (pinfunction "HVout47/18_58") (pintype "passive"))
    )
    (net (code "79") (name "/OUT6-4") (class "Default")
      (node (ref "N6") (pin "6") (pinfunction "Cathode_\"4\"_6") (pintype "passive"))
      (node (ref "U1") (pin "57") (pinfunction "HVout48/17_57") (pintype "passive"))
    )
    (net (code "80") (name "/OUT6-5") (class "Default")
      (node (ref "N6") (pin "7") (pinfunction "Cathode_\"5\"_7") (pintype "passive"))
      (node (ref "U1") (pin "56") (pinfunction "HVout49/16_56") (pintype "passive"))
    )
    (net (code "81") (name "/OUT6-6") (class "Default")
      (node (ref "N6") (pin "8") (pinfunction "Cathode_\"6\"_8") (pintype "passive"))
      (node (ref "U1") (pin "55") (pinfunction "HVout50/15_55") (pintype "passive"))
    )
    (net (code "82") (name "/OUT6-7") (class "Default")
      (node (ref "N6") (pin "9") (pinfunction "Cathode_\"7\"_9") (pintype "passive"))
      (node (ref "U1") (pin "54") (pinfunction "HVout51/14_54") (pintype "passive"))
    )
    (net (code "83") (name "/OUT6-8") (class "Default")
      (node (ref "N6") (pin "10") (pinfunction "Cathode_\"8\"_10") (pintype "passive"))
      (node (ref "U1") (pin "53") (pinfunction "HVout52/13_53") (pintype "passive"))
    )
    (net (code "84") (name "/OUT6-9") (class "Default")
      (node (ref "N6") (pin "11") (pinfunction "Cathode_\"9\"_11") (pintype "passive"))
      (node (ref "U1") (pin "52") (pinfunction "HVout53/12_52") (pintype "passive"))
    )
    (net (code "85") (name "/OUT6-10") (class "Default")
      (node (ref "N6") (pin "12") (pinfunction "Cathode_\"0\"_12") (pintype "passive"))
      (node (ref "U1") (pin "51") (pinfunction "HVout54/11_51") (pintype "passive"))
    )
    (net (code "86") (name "/RX0") (class "Default")
      (node (ref "M1") (pin "5") (pinfunction "TXD_5") (pintype "passive"))
      (node (ref "U3") (pin "43") (pinfunction "PB7/I2C1_SDA/TIM4_CH2/USART1_RX_43") (pintype "passive"))
    )
    (net (code "87") (name "/SCL") (class "Default")
      (node (ref "IC1") (pin "6") (pinfunction "SCL_6") (pintype "passive"))
      (node (ref "R51") (pin "2") (pinfunction "2_2") (pintype "passive"))
      (node (ref "U11") (pin "16") (pinfunction "SCL_16") (pintype "passive"))
      (node (ref "U3") (pin "46") (pinfunction "PB9/TIM4_CH4/I2C1_SDA/CANTX_46") (pintype "passive"))
    )
    (net (code "88") (name "/SDA") (class "Default")
      (node (ref "IC1") (pin "5") (pinfunction "SDA_5") (pintype "passive"))
      (node (ref "R52") (pin "2") (pinfunction "2_2") (pintype "passive"))
      (node (ref "U11") (pin "15") (pinfunction "SDA_15") (pintype "passive"))
      (node (ref "U3") (pin "45") (pinfunction "PB8/TIM4_CH3/I2C1_SCL/CANRX_45") (pintype "passive"))
    )
    (net (code "89") (name "/SWCLK") (class "Default")
      (node (ref "JP1") (pin "5") (pinfunction "5_5") (pintype "passive"))
      (node (ref "U3") (pin "37") (pinfunction "PA14/JTCK-SWCLK_37") (pintype "passive"))
    )
    (net (code "90") (name "/SWDAT") (class "Default")
      (node (ref "JP1") (pin "4") (pinfunction "4_4") (pintype "passive"))
      (node (ref "U3") (pin "34") (pinfunction "PA13/JTMS-SWDAT_34") (pintype "passive"))
    )
    (net (code "91") (name "/TX0") (class "Default")
      (node (ref "M1") (pin "4") (pinfunction "RXD_4") (pintype "passive"))
      (node (ref "U3") (pin "42") (pinfunction "PB6/I2C1_SCL/TIM4_CH1/USART1_TX_42") (pintype "passive"))
    )
    (net (code "92") (name "/WP") (class "Default")
      (node (ref "U3") (pin "41") (pinfunction "PB5/TIM3_CH2/SPI1_MOSI_41") (pintype "passive"))
    )
    (net (code "93") (name "3.3V") (class "Default")
      (node (ref "C10") (pin "2") (pinfunction "2_2") (pintype "passive"))
      (node (ref "C14") (pin "1") (pinfunction "1_1") (pintype "passive"))
      (node (ref "C9") (pin "2") (pinfunction "2_2") (pintype "passive"))
      (node (ref "IC1") (pin "8") (pinfunction "VCC_8") (pintype "power_in"))
      (node (ref "M1") (pin "6") (pinfunction "VCC_6") (pintype "passive"))
      (node (ref "R36") (pin "2") (pinfunction "2_2") (pintype "passive"))
      (node (ref "R37") (pin "2") (pinfunction "2_2") (pintype "passive"))
      (node (ref "R43") (pin "2") (pinfunction "2_2") (pintype "passive"))
      (node (ref "R51") (pin "1") (pinfunction "1_1") (pintype "passive"))
      (node (ref "R52") (pin "1") (pinfunction "1_1") (pintype "passive"))
      (node (ref "U11") (pin "2") (pinfunction "VCC_2") (pintype "passive"))
      (node (ref "U11") (pin "4") (pinfunction "RST_4") (pintype "passive"))
      (node (ref "U3") (pin "1") (pinfunction "VBAT_1") (pintype "passive"))
      (node (ref "U3") (pin "24") (pinfunction "VDD_1_24") (pintype "passive"))
      (node (ref "U3") (pin "36") (pinfunction "VDD_2_36") (pintype "passive"))
      (node (ref "U3") (pin "48") (pinfunction "VDD_3_48") (pintype "passive"))
      (node (ref "U3") (pin "9") (pinfunction "VDDA_9") (pintype "passive"))
      (node (ref "V1") (pin "2") (pinfunction "Vout_2") (pintype "passive"))
    )
    (net (code "94") (name "5V") (class "Default")
      (node (ref "C16") (pin "2") (pinfunction "2_2") (pintype "passive"))
      (node (ref "C18") (pin "2") (pinfunction "2_2") (pintype "passive"))
      (node (ref "C2") (pin "2") (pinfunction "2_2") (pintype "passive"))
      (node (ref "C3") (pin "2") (pinfunction "2_2") (pintype "passive"))
      (node (ref "C4") (pin "2") (pinfunction "2_2") (pintype "passive"))
      (node (ref "C8") (pin "2") (pinfunction "2_2") (pintype "passive"))
      (node (ref "R18") (pin "1") (pinfunction "1_1") (pintype "passive"))
      (node (ref "R18") (pin "2") (pinfunction "2_2") (pintype "passive"))
      (node (ref "R18") (pin "3") (pinfunction "3_3") (pintype "passive"))
      (node (ref "R18") (pin "4") (pinfunction "4_4") (pintype "passive"))
      (node (ref "R21") (pin "1") (pinfunction "1_1") (pintype "passive"))
      (node (ref "R21") (pin "2") (pinfunction "2_2") (pintype "passive"))
      (node (ref "R21") (pin "3") (pinfunction "3_3") (pintype "passive"))
      (node (ref "R21") (pin "4") (pinfunction "4_4") (pintype "passive"))
      (node (ref "T1") (pin "2") (pinfunction "2_2") (pintype "passive"))
      (node (ref "U1") (pin "31") (pinfunction "~{B}L_31") (pintype "passive"))
      (node (ref "U1") (pin "32") (pinfunction "VDD_32") (pintype "passive"))
      (node (ref "U1") (pin "33") (pinfunction "DIR_33") (pintype "passive"))
      (node (ref "U2") (pin "8") (pinfunction "VIN_8") (pintype "passive"))
      (node (ref "USB1") (pin "1") (pinfunction "+5V_1") (pintype "passive"))
      (node (ref "V1") (pin "3") (pinfunction "Vin_3") (pintype "passive"))
    )
    (net (code "95") (name "GND") (class "Default")
      (node (ref "B1") (pin "2") (pinfunction "2_2") (pintype "passive"))
      (node (ref "C1") (pin "1") (pinfunction "1_1") (pintype "passive"))
      (node (ref "C10") (pin "1") (pinfunction "1_1") (pintype "passive"))
      (node (ref "C11") (pin "2") (pinfunction "2_2") (pintype "passive"))
      (node (ref "C12") (pin "1") (pinfunction "1_1") (pintype "passive"))
      (node (ref "C13") (pin "1") (pinfunction "1_1") (pintype "passive"))
      (node (ref "C14") (pin "2") (pinfunction "2_2") (pintype "passive"))
      (node (ref "C15") (pin "2") (pinfunction "2_2") (pintype "passive"))
      (node (ref "C16") (pin "1") (pinfunction "1_1") (pintype "passive"))
      (node (ref "C17") (pin "1") (pinfunction "1_1") (pintype "passive"))
      (node (ref "C18") (pin "1") (pinfunction "1_1") (pintype "passive"))
      (node (ref "C2") (pin "1") (pinfunction "1_1") (pintype "passive"))
      (node (ref "C3") (pin "1") (pinfunction "1_1") (pintype "passive"))
      (node (ref "C4") (pin "1") (pinfunction "1_1") (pintype "passive"))
      (node (ref "C6") (pin "2") (pinfunction "2_2") (pintype "passive"))
      (node (ref "C7") (pin "1") (pinfunction "1_1") (pintype "passive"))
      (node (ref "C8") (pin "1") (pinfunction "1_1") (pintype "passive"))
      (node (ref "C9") (pin "1") (pinfunction "1_1") (pintype "passive"))
      (node (ref "CR1") (pin "2") (pinfunction "DC-_2") (pintype "passive"))
      (node (ref "D1") (pin "1") (pinfunction "A_1") (pintype "passive"))
      (node (ref "IC1") (pin "1") (pinfunction "A0_1") (pintype "input"))
      (node (ref "IC1") (pin "2") (pinfunction "A1_2") (pintype "input"))
      (node (ref "IC1") (pin "3") (pinfunction "A2_3") (pintype "input"))
      (node (ref "IC1") (pin "4") (pinfunction "GND_4") (pintype "passive"))
      (node (ref "IC1") (pin "7") (pinfunction "WP_7") (pintype "passive"))
      (node (ref "JP1") (pin "1") (pinfunction "1_1") (pintype "passive"))
      (node (ref "M1") (pin "1") (pinfunction "GND_1") (pintype "passive"))
      (node (ref "M1") (pin "2") (pinfunction "GND_2") (pintype "passive"))
      (node (ref "M1") (pin "3") (pinfunction "GND_3") (pintype "passive"))
      (node (ref "Q10") (pin "2") (pinfunction "E_2") (pintype "passive"))
      (node (ref "Q2") (pin "2") (pinfunction "E_2") (pintype "passive"))
      (node (ref "Q3") (pin "2") (pinfunction "E_2") (pintype "passive"))
      (node (ref "Q4") (pin "2") (pinfunction "E_2") (pintype "passive"))
      (node (ref "Q5") (pin "2") (pinfunction "E_2") (pintype "passive"))
      (node (ref "Q6") (pin "2") (pinfunction "E_2") (pintype "passive"))
      (node (ref "Q7") (pin "2") (pinfunction "E_2") (pintype "passive"))
      (node (ref "Q8") (pin "2") (pinfunction "E_2") (pintype "passive"))
      (node (ref "R4") (pin "1") (pinfunction "1_1") (pintype "passive"))
      (node (ref "R50") (pin "2") (pinfunction "2_2") (pintype "passive"))
      (node (ref "R7") (pin "1") (pinfunction "1_1") (pintype "passive"))
      (node (ref "R8") (pin "2") (pinfunction "2_2") (pintype "passive"))
      (node (ref "R9") (pin "2") (pinfunction "2_2") (pintype "passive"))
      (node (ref "SW1") (pin "2") (pinfunction "2_2") (pintype "passive"))
      (node (ref "SW2") (pin "2") (pinfunction "2_2") (pintype "passive"))
      (node (ref "SW3") (pin "2") (pinfunction "2_2") (pintype "passive"))
      (node (ref "TP1") (pin "1") (pinfunction "1_1") (pintype "passive"))
      (node (ref "U1") (pin "34") (pinfunction "GND_34") (pintype "passive"))
      (node (ref "U1") (pin "35") (pinfunction "~{PO}L_35") (pintype "passive"))
      (node (ref "U11") (pin "10") (pinfunction "NC_10") (pintype "passive"))
      (node (ref "U11") (pin "11") (pinfunction "NC_11") (pintype "passive"))
      (node (ref "U11") (pin "12") (pinfunction "NC_12") (pintype "passive"))
      (node (ref "U11") (pin "13") (pinfunction "GND_13") (pintype "passive"))
      (node (ref "U11") (pin "5") (pinfunction "NC_5") (pintype "passive"))
      (node (ref "U11") (pin "6") (pinfunction "NC_6") (pintype "passive"))
      (node (ref "U11") (pin "7") (pinfunction "NC_7") (pintype "passive"))
      (node (ref "U11") (pin "8") (pinfunction "NC_8") (pintype "passive"))
      (node (ref "U11") (pin "9") (pinfunction "NC_9") (pintype "passive"))
      (node (ref "U2") (pin "4") (pinfunction "AGND_4") (pintype "passive"))
      (node (ref "U2") (pin "5") (pinfunction "PGND_5") (pintype "passive"))
      (node (ref "U3") (pin "20") (pinfunction "PB2/BOOT1_20") (pintype "passive"))
      (node (ref "U3") (pin "23") (pinfunction "VSS_1_23") (pintype "passive"))
      (node (ref "U3") (pin "35") (pinfunction "VSS_2_35") (pintype "passive"))
      (node (ref "U3") (pin "47") (pinfunction "VSS_3_47") (pintype "passive"))
      (node (ref "U3") (pin "8") (pinfunction "VSSA_8") (pintype "passive"))
      (node (ref "USB1") (pin "5") (pinfunction "GND_5") (pintype "passive"))
      (node (ref "V1") (pin "1") (pinfunction "GND_1") (pintype "passive"))
    )
    (net (code "96") (name "HV") (class "Default")
      (node (ref "C1") (pin "2") (pinfunction "2_2") (pintype "passive"))
      (node (ref "C17") (pin "2") (pinfunction "2_2") (pintype "passive"))
      (node (ref "D2") (pin "2") (pinfunction "K_2") (pintype "passive"))
      (node (ref "R1") (pin "2") (pinfunction "2_2") (pintype "passive"))
      (node (ref "R10") (pin "2") (pinfunction "2_2") (pintype "passive"))
      (node (ref "R11") (pin "2") (pinfunction "2_2") (pintype "passive"))
      (node (ref "R12") (pin "2") (pinfunction "2_2") (pintype "passive"))
      (node (ref "R13") (pin "2") (pinfunction "2_2") (pintype "passive"))
      (node (ref "R16") (pin "1") (pinfunction "1_1") (pintype "passive"))
      (node (ref "R17") (pin "1") (pinfunction "1_1") (pintype "passive"))
      (node (ref "R2") (pin "2") (pinfunction "2_2") (pintype "passive"))
      (node (ref "R22") (pin "1") (pinfunction "1_1") (pintype "passive"))
      (node (ref "R23") (pin "1") (pinfunction "1_1") (pintype "passive"))
      (node (ref "R3") (pin "1") (pinfunction "1_1") (pintype "passive"))
      (node (ref "R5") (pin "1") (pinfunction "1_1") (pintype "passive"))
    )
    (net (code "97") (name "Net-(C5-Pad1)") (class "Default")
      (node (ref "C5") (pin "1") (pinfunction "1_1") (pintype "passive"))
      (node (ref "R8") (pin "1") (pinfunction "1_1") (pintype "passive"))
    )
    (net (code "98") (name "Net-(C6-Pad1)") (class "Default")
      (node (ref "C6") (pin "1") (pinfunction "1_1") (pintype "passive"))
      (node (ref "Q1") (pin "1") (pinfunction "S_1") (pintype "power_in"))
      (node (ref "Q1") (pin "2") (pinfunction "S_2") (pintype "power_in"))
      (node (ref "Q1") (pin "3") (pinfunction "S_3") (pintype "power_in"))
      (node (ref "R53") (pin "2") (pinfunction "2_2") (pintype "passive"))
      (node (ref "R7") (pin "2") (pinfunction "2_2") (pintype "passive"))
    )
    (net (code "99") (name "Net-(CR1-DC+)") (class "Default")
      (node (ref "CR1") (pin "1") (pinfunction "DC+_1") (pintype "passive"))
      (node (ref "U11") (pin "14") (pinfunction "VBAT_14") (pintype "passive"))
    )
    (net (code "100") (name "Net-(D1-K)") (class "Default")
      (node (ref "D1") (pin "2") (pinfunction "K_2") (pintype "passive"))
      (node (ref "R3") (pin "2") (pinfunction "2_2") (pintype "passive"))
      (node (ref "U1") (pin "40") (pinfunction "VPP_40") (pintype "passive"))
    )
    (net (code "101") (name "Net-(D2-A)") (class "Default")
      (node (ref "D2") (pin "1") (pinfunction "A_1") (pintype "passive"))
      (node (ref "T1") (pin "4") (pinfunction "4_4") (pintype "passive"))
    )
    (net (code "102") (name "Net-(DS1-Pad2)") (class "Default")
      (node (ref "DS1") (pin "2") (pinfunction "2_2") (pintype "passive"))
      (node (ref "R16") (pin "2") (pinfunction "2_2") (pintype "passive"))
    )
    (net (code "103") (name "Net-(DS2-Pad2)") (class "Default")
      (node (ref "DS2") (pin "2") (pinfunction "2_2") (pintype "passive"))
      (node (ref "R17") (pin "2") (pinfunction "2_2") (pintype "passive"))
    )
    (net (code "104") (name "Net-(DS3-Pad2)") (class "Default")
      (node (ref "DS3") (pin "2") (pinfunction "2_2") (pintype "passive"))
      (node (ref "R22") (pin "2") (pinfunction "2_2") (pintype "passive"))
    )
    (net (code "105") (name "Net-(DS4-Pad2)") (class "Default")
      (node (ref "DS4") (pin "2") (pinfunction "2_2") (pintype "passive"))
      (node (ref "R23") (pin "2") (pinfunction "2_2") (pintype "passive"))
    )
    (net (code "106") (name "Net-(N1-Anode)") (class "Default")
      (node (ref "N1") (pin "1") (pinfunction "Anode_1") (pintype "passive"))
      (node (ref "R1") (pin "1") (pinfunction "1_1") (pintype "passive"))
    )
    (net (code "107") (name "Net-(N2-Anode)") (class "Default")
      (node (ref "N2") (pin "1") (pinfunction "Anode_1") (pintype "passive"))
      (node (ref "R2") (pin "1") (pinfunction "1_1") (pintype "passive"))
    )
    (net (code "108") (name "Net-(N3-Anode)") (class "Default")
      (node (ref "N3") (pin "1") (pinfunction "Anode_1") (pintype "passive"))
      (node (ref "R10") (pin "1") (pinfunction "1_1") (pintype "passive"))
    )
    (net (code "109") (name "Net-(N4-Anode)") (class "Default")
      (node (ref "N4") (pin "1") (pinfunction "Anode_1") (pintype "passive"))
      (node (ref "R11") (pin "1") (pinfunction "1_1") (pintype "passive"))
    )
    (net (code "110") (name "Net-(N5-Anode)") (class "Default")
      (node (ref "N5") (pin "1") (pinfunction "Anode_1") (pintype "passive"))
      (node (ref "R12") (pin "1") (pinfunction "1_1") (pintype "passive"))
    )
    (net (code "111") (name "Net-(N6-Anode)") (class "Default")
      (node (ref "N6") (pin "1") (pinfunction "Anode_1") (pintype "passive"))
      (node (ref "R13") (pin "1") (pinfunction "1_1") (pintype "passive"))
    )
    (net (code "112") (name "Net-(Q1-D-Pad5)") (class "Default")
      (node (ref "Q1") (pin "5") (pinfunction "D_5") (pintype "power_in"))
      (node (ref "Q1") (pin "6") (pinfunction "D_6") (pintype "power_in"))
      (node (ref "Q1") (pin "7") (pinfunction "D_7") (pintype "power_in"))
      (node (ref "Q1") (pin "8") (pinfunction "D_8") (pintype "power_in"))
      (node (ref "T1") (pin "1") (pinfunction "1_1") (pintype "passive"))
      (node (ref "T1") (pin "3") (pinfunction "3_3") (pintype "passive"))
    )
    (net (code "113") (name "Net-(Q1-G)") (class "Default")
      (node (ref "Q1") (pin "4") (pinfunction "G_4") (pintype "power_in"))
      (node (ref "R4") (pin "2") (pinfunction "2_2") (pintype "passive"))
      (node (ref "R6") (pin "2") (pinfunction "2_2") (pintype "passive"))
    )
    (net (code "114") (name "Net-(Q2-B)") (class "Default")
      (node (ref "Q2") (pin "1") (pinfunction "B_1") (pintype "passive"))
      (node (ref "R14") (pin "1") (pinfunction "1_1") (pintype "passive"))
    )
    (net (code "115") (name "Net-(Q2-C)") (class "Default")
      (node (ref "DS1") (pin "1") (pinfunction "1_1") (pintype "passive"))
      (node (ref "Q2") (pin "3") (pinfunction "C_3") (pintype "passive"))
    )
    (net (code "116") (name "Net-(Q3-B)") (class "Default")
      (node (ref "Q3") (pin "1") (pinfunction "B_1") (pintype "passive"))
      (node (ref "R15") (pin "1") (pinfunction "1_1") (pintype "passive"))
    )
    (net (code "117") (name "Net-(Q3-C)") (class "Default")
      (node (ref "DS2") (pin "1") (pinfunction "1_1") (pintype "passive"))
      (node (ref "Q3") (pin "3") (pinfunction "C_3") (pintype "passive"))
    )
    (net (code "118") (name "Net-(Q4-B)") (class "Default")
      (node (ref "Q4") (pin "1") (pinfunction "B_1") (pintype "passive"))
      (node (ref "R19") (pin "1") (pinfunction "1_1") (pintype "passive"))
    )
    (net (code "119") (name "Net-(Q4-C)") (class "Default")
      (node (ref "DS3") (pin "1") (pinfunction "1_1") (pintype "passive"))
      (node (ref "Q4") (pin "3") (pinfunction "C_3") (pintype "passive"))
    )
    (net (code "120") (name "Net-(Q5-B)") (class "Default")
      (node (ref "Q5") (pin "1") (pinfunction "B_1") (pintype "passive"))
      (node (ref "R20") (pin "1") (pinfunction "1_1") (pintype "passive"))
    )
    (net (code "121") (name "Net-(Q5-C)") (class "Default")
      (node (ref "DS4") (pin "1") (pinfunction "1_1") (pintype "passive"))
      (node (ref "Q5") (pin "3") (pinfunction "C_3") (pintype "passive"))
    )
    (net (code "122") (name "Net-(Q6-B)") (class "Default")
      (node (ref "Q6") (pin "1") (pinfunction "B_1") (pintype "passive"))
      (node (ref "R24") (pin "1") (pinfunction "1_1") (pintype "passive"))
    )
    (net (code "123") (name "Net-(Q7-B)") (class "Default")
      (node (ref "Q7") (pin "1") (pinfunction "B_1") (pintype "passive"))
      (node (ref "R25") (pin "1") (pinfunction "1_1") (pintype "passive"))
    )
    (net (code "124") (name "Net-(Q8-B)") (class "Default")
      (node (ref "Q8") (pin "1") (pinfunction "B_1") (pintype "passive"))
      (node (ref "R26") (pin "1") (pinfunction "1_1") (pintype "passive"))
    )
    (net (code "125") (name "Net-(Q9-B)") (class "Default")
      (node (ref "Q9") (pin "1") (pinfunction "B_1") (pintype "passive"))
      (node (ref "R33") (pin "2") (pinfunction "2_2") (pintype "passive"))
    )
    (net (code "126") (name "Net-(Q9-C)") (class "Default")
      (node (ref "Q9") (pin "3") (pinfunction "C_3") (pintype "passive"))
      (node (ref "R37") (pin "1") (pinfunction "1_1") (pintype "passive"))
    )
    (net (code "127") (name "Net-(Q9-E)") (class "Default")
      (node (ref "B1") (pin "1") (pinfunction "1_1") (pintype "passive"))
      (node (ref "Q9") (pin "2") (pinfunction "E_2") (pintype "passive"))
    )
    (net (code "128") (name "Net-(Q10-B)") (class "Default")
      (node (ref "Q10") (pin "1") (pinfunction "B_1") (pintype "passive"))
      (node (ref "R54") (pin "1") (pinfunction "1_1") (pintype "passive"))
    )
    (net (code "129") (name "Net-(Q10-C)") (class "Default")
      (node (ref "C5") (pin "2") (pinfunction "2_2") (pintype "passive"))
      (node (ref "C7") (pin "2") (pinfunction "2_2") (pintype "passive"))
      (node (ref "Q10") (pin "3") (pinfunction "C_3") (pintype "passive"))
      (node (ref "U2") (pin "2") (pinfunction "COMP_2") (pintype "passive"))
    )
    (net (code "130") (name "Net-(R36-Pad1)") (class "Default")
      (node (ref "R36") (pin "1") (pinfunction "1_1") (pintype "passive"))
      (node (ref "R38") (pin "2") (pinfunction "2_2") (pintype "passive"))
      (node (ref "TP1") (pin "2") (pinfunction "2_2") (pintype "passive"))
    )
    (net (code "131") (name "Net-(U2-DR)") (class "Default")
      (node (ref "R6") (pin "1") (pinfunction "1_1") (pintype "passive"))
      (node (ref "U2") (pin "6") (pinfunction "DR_6") (pintype "passive"))
    )
    (net (code "132") (name "Net-(U2-FA{slash}SD)") (class "Default")
      (node (ref "R9") (pin "1") (pinfunction "1_1") (pintype "passive"))
      (node (ref "U2") (pin "7") (pinfunction "FA/SD_7") (pintype "passive"))
    )
    (net (code "133") (name "Net-(U2-FB)") (class "Default")
      (node (ref "C15") (pin "1") (pinfunction "1_1") (pintype "passive"))
      (node (ref "R5") (pin "2") (pinfunction "2_2") (pintype "passive"))
      (node (ref "R50") (pin "1") (pinfunction "1_1") (pintype "passive"))
      (node (ref "U2") (pin "3") (pinfunction "FB_3") (pintype "passive"))
    )
    (net (code "134") (name "Net-(U2-ISEN)") (class "Default")
      (node (ref "R53") (pin "1") (pinfunction "1_1") (pintype "passive"))
      (node (ref "U2") (pin "1") (pinfunction "ISEN_1") (pintype "passive"))
    )
    (net (code "135") (name "Net-(U3-NRST)") (class "Default")
      (node (ref "C13") (pin "2") (pinfunction "2_2") (pintype "passive"))
      (node (ref "R43") (pin "1") (pinfunction "1_1") (pintype "passive"))
      (node (ref "U3") (pin "7") (pinfunction "NRST_7") (pintype "passive"))
    )
    (net (code "136") (name "Net-(U3-PD0{slash}OSC_IN)") (class "Default")
      (node (ref "C11") (pin "1") (pinfunction "1_1") (pintype "passive"))
      (node (ref "U3") (pin "5") (pinfunction "PD0/OSC_IN_5") (pintype "passive"))
      (node (ref "X1") (pin "1") (pinfunction "OSC1_1") (pintype "passive"))
    )
    (net (code "137") (name "Net-(U3-PD1{slash}OSC_OUT)") (class "Default")
      (node (ref "C12") (pin "2") (pinfunction "2_2") (pintype "passive"))
      (node (ref "U3") (pin "6") (pinfunction "PD1/OSC_OUT_6") (pintype "passive"))
      (node (ref "X1") (pin "2") (pinfunction "OSC2_2") (pintype "passive"))
    )
    (net (code "138") (name "unconnected-(N1-Cathode_comma-Pad2)") (class "Default")
      (node (ref "N1") (pin "2") (pinfunction "Cathode_comma_2") (pintype "passive"))
    )
    (net (code "139") (name "unconnected-(N1-Cathode_comma-Pad13)") (class "Default")
      (node (ref "N1") (pin "13") (pinfunction "Cathode_comma_13") (pintype "passive"))
    )
    (net (code "140") (name "unconnected-(N2-Cathode_comma-Pad2)") (class "Default")
      (node (ref "N2") (pin "2") (pinfunction "Cathode_comma_2") (pintype "passive"))
    )
    (net (code "141") (name "unconnected-(N2-Cathode_comma-Pad13)") (class "Default")
      (node (ref "N2") (pin "13") (pinfunction "Cathode_comma_13") (pintype "passive"))
    )
    (net (code "142") (name "unconnected-(N3-Cathode_comma-Pad2)") (class "Default")
      (node (ref "N3") (pin "2") (pinfunction "Cathode_comma_2") (pintype "passive"))
    )
    (net (code "143") (name "unconnected-(N3-Cathode_comma-Pad13)") (class "Default")
      (node (ref "N3") (pin "13") (pinfunction "Cathode_comma_13") (pintype "passive"))
    )
    (net (code "144") (name "unconnected-(N4-Cathode_comma-Pad2)") (class "Default")
      (node (ref "N4") (pin "2") (pinfunction "Cathode_comma_2") (pintype "passive"))
    )
    (net (code "145") (name "unconnected-(N4-Cathode_comma-Pad13)") (class "Default")
      (node (ref "N4") (pin "13") (pinfunction "Cathode_comma_13") (pintype "passive"))
    )
    (net (code "146") (name "unconnected-(N5-Cathode_comma-Pad2)") (class "Default")
      (node (ref "N5") (pin "2") (pinfunction "Cathode_comma_2") (pintype "passive"))
    )
    (net (code "147") (name "unconnected-(N5-Cathode_comma-Pad13)") (class "Default")
      (node (ref "N5") (pin "13") (pinfunction "Cathode_comma_13") (pintype "passive"))
    )
    (net (code "148") (name "unconnected-(N6-Cathode_comma-Pad2)") (class "Default")
      (node (ref "N6") (pin "2") (pinfunction "Cathode_comma_2") (pintype "passive"))
    )
    (net (code "149") (name "unconnected-(N6-Cathode_comma-Pad13)") (class "Default")
      (node (ref "N6") (pin "13") (pinfunction "Cathode_comma_13") (pintype "passive"))
    )
    (net (code "150") (name "unconnected-(R18-Pad5)") (class "Default")
      (node (ref "R18") (pin "5") (pinfunction "5_5") (pintype "passive"))
    )
    (net (code "151") (name "unconnected-(R18-Pad6)") (class "Default")
      (node (ref "R18") (pin "6") (pinfunction "6_6") (pintype "passive"))
    )
    (net (code "152") (name "unconnected-(U1-Dout1{slash}Din4(B)-Pad39)") (class "Default")
      (node (ref "U1") (pin "39") (pinfunction "Dout1/Din4(B)_39") (pintype "passive"))
    )
    (net (code "153") (name "unconnected-(U1-Dout2{slash}Din3(B)-Pad38)") (class "Default")
      (node (ref "U1") (pin "38") (pinfunction "Dout2/Din3(B)_38") (pintype "passive"))
    )
    (net (code "154") (name "unconnected-(U1-Dout3{slash}Din2(B)-Pad37)") (class "Default")
      (node (ref "U1") (pin "37") (pinfunction "Dout3/Din2(B)_37") (pintype "passive"))
    )
    (net (code "155") (name "unconnected-(U1-Dout4{slash}Din1(B)-Pad36)") (class "Default")
      (node (ref "U1") (pin "36") (pinfunction "Dout4/Din1(B)_36") (pintype "passive"))
    )
    (net (code "156") (name "unconnected-(U1-HVout31{slash}34-Pad74)") (class "Default")
      (node (ref "U1") (pin "74") (pinfunction "HVout31/34_74") (pintype "passive"))
    )
    (net (code "157") (name "unconnected-(U1-HVout32{slash}33-Pad73)") (class "Default")
      (node (ref "U1") (pin "73") (pinfunction "HVout32/33_73") (pintype "passive"))
    )
    (net (code "158") (name "unconnected-(U1-HVout33{slash}32-Pad72)") (class "Default")
      (node (ref "U1") (pin "72") (pinfunction "HVout33/32_72") (pintype "passive"))
    )
    (net (code "159") (name "unconnected-(U1-HVout34{slash}31-Pad71)") (class "Default")
      (node (ref "U1") (pin "71") (pinfunction "HVout34/31_71") (pintype "passive"))
    )
    (net (code "160") (name "unconnected-(U3-PA0{slash}WKUP{slash}USART2_STS{slash}ADC_IN0{slash}TIM2_CH1_ETR-Pad10)") (class "Default")
      (node (ref "U3") (pin "10") (pinfunction "PA0/WKUP/USART2_STS/ADC_IN0/TIM2_CH1_ETR_10") (pintype "passive"))
    )
    (net (code "161") (name "unconnected-(U3-PA1{slash}{slash}USART2_RTS{slash}ADC_IN1{slash}TIM2_CH2-Pad11)") (class "Default")
      (node (ref "U3") (pin "11") (pinfunction "PA1//USART2_RTS/ADC_IN1/TIM2_CH2_11") (pintype "passive"))
    )
    (net (code "162") (name "unconnected-(U3-PA2{slash}{slash}USART2_TX{slash}ADC_IN2{slash}TIM2_CH3-Pad12)") (class "Default")
      (node (ref "U3") (pin "12") (pinfunction "PA2//USART2_TX/ADC_IN2/TIM2_CH3_12") (pintype "passive"))
    )
    (net (code "163") (name "unconnected-(U3-PA15{slash}JTDI{slash}TIM2_CH1{slash}SP11_NSS-Pad38)") (class "Default")
      (node (ref "U3") (pin "38") (pinfunction "PA15/JTDI/TIM2_CH1/SP11_NSS_38") (pintype "passive"))
    )
    (net (code "164") (name "unconnected-(U3-PB3{slash}JTDO{slash}TIM2_CH2{slash}SPI1_SCK-Pad39)") (class "Default")
      (node (ref "U3") (pin "39") (pinfunction "PB3/JTDO/TIM2_CH2/SPI1_SCK_39") (pintype "passive"))
    )
    (net (code "165") (name "unconnected-(U3-PC15{slash}OSC32_OUT-Pad4)") (class "Default")
      (node (ref "U3") (pin "4") (pinfunction "PC15/OSC32_OUT_4") (pintype "passive"))
    )
    (net (code "166") (name "unconnected-(U11-32KHZ-Pad1)") (class "Default")
      (node (ref "U11") (pin "1") (pinfunction "32KHZ_1") (pintype "passive"))
    )
    (net (code "167") (name "unconnected-(USB1-D+-Pad3)") (class "Default")
      (node (ref "USB1") (pin "3") (pinfunction "D+_3") (pintype "passive"))
    )
    (net (code "168") (name "unconnected-(USB1-D--Pad2)") (class "Default")
      (node (ref "USB1") (pin "2") (pinfunction "D-_2") (pintype "passive"))
    )
    (net (code "169") (name "unconnected-(USB1-ID-Pad4)") (class "Default")
      (node (ref "USB1") (pin "4") (pinfunction "ID_4") (pintype "passive"))
    )
  )
)
